# ledboard-r1.net
KiCad netlist of a schematic drawn in EAGLE
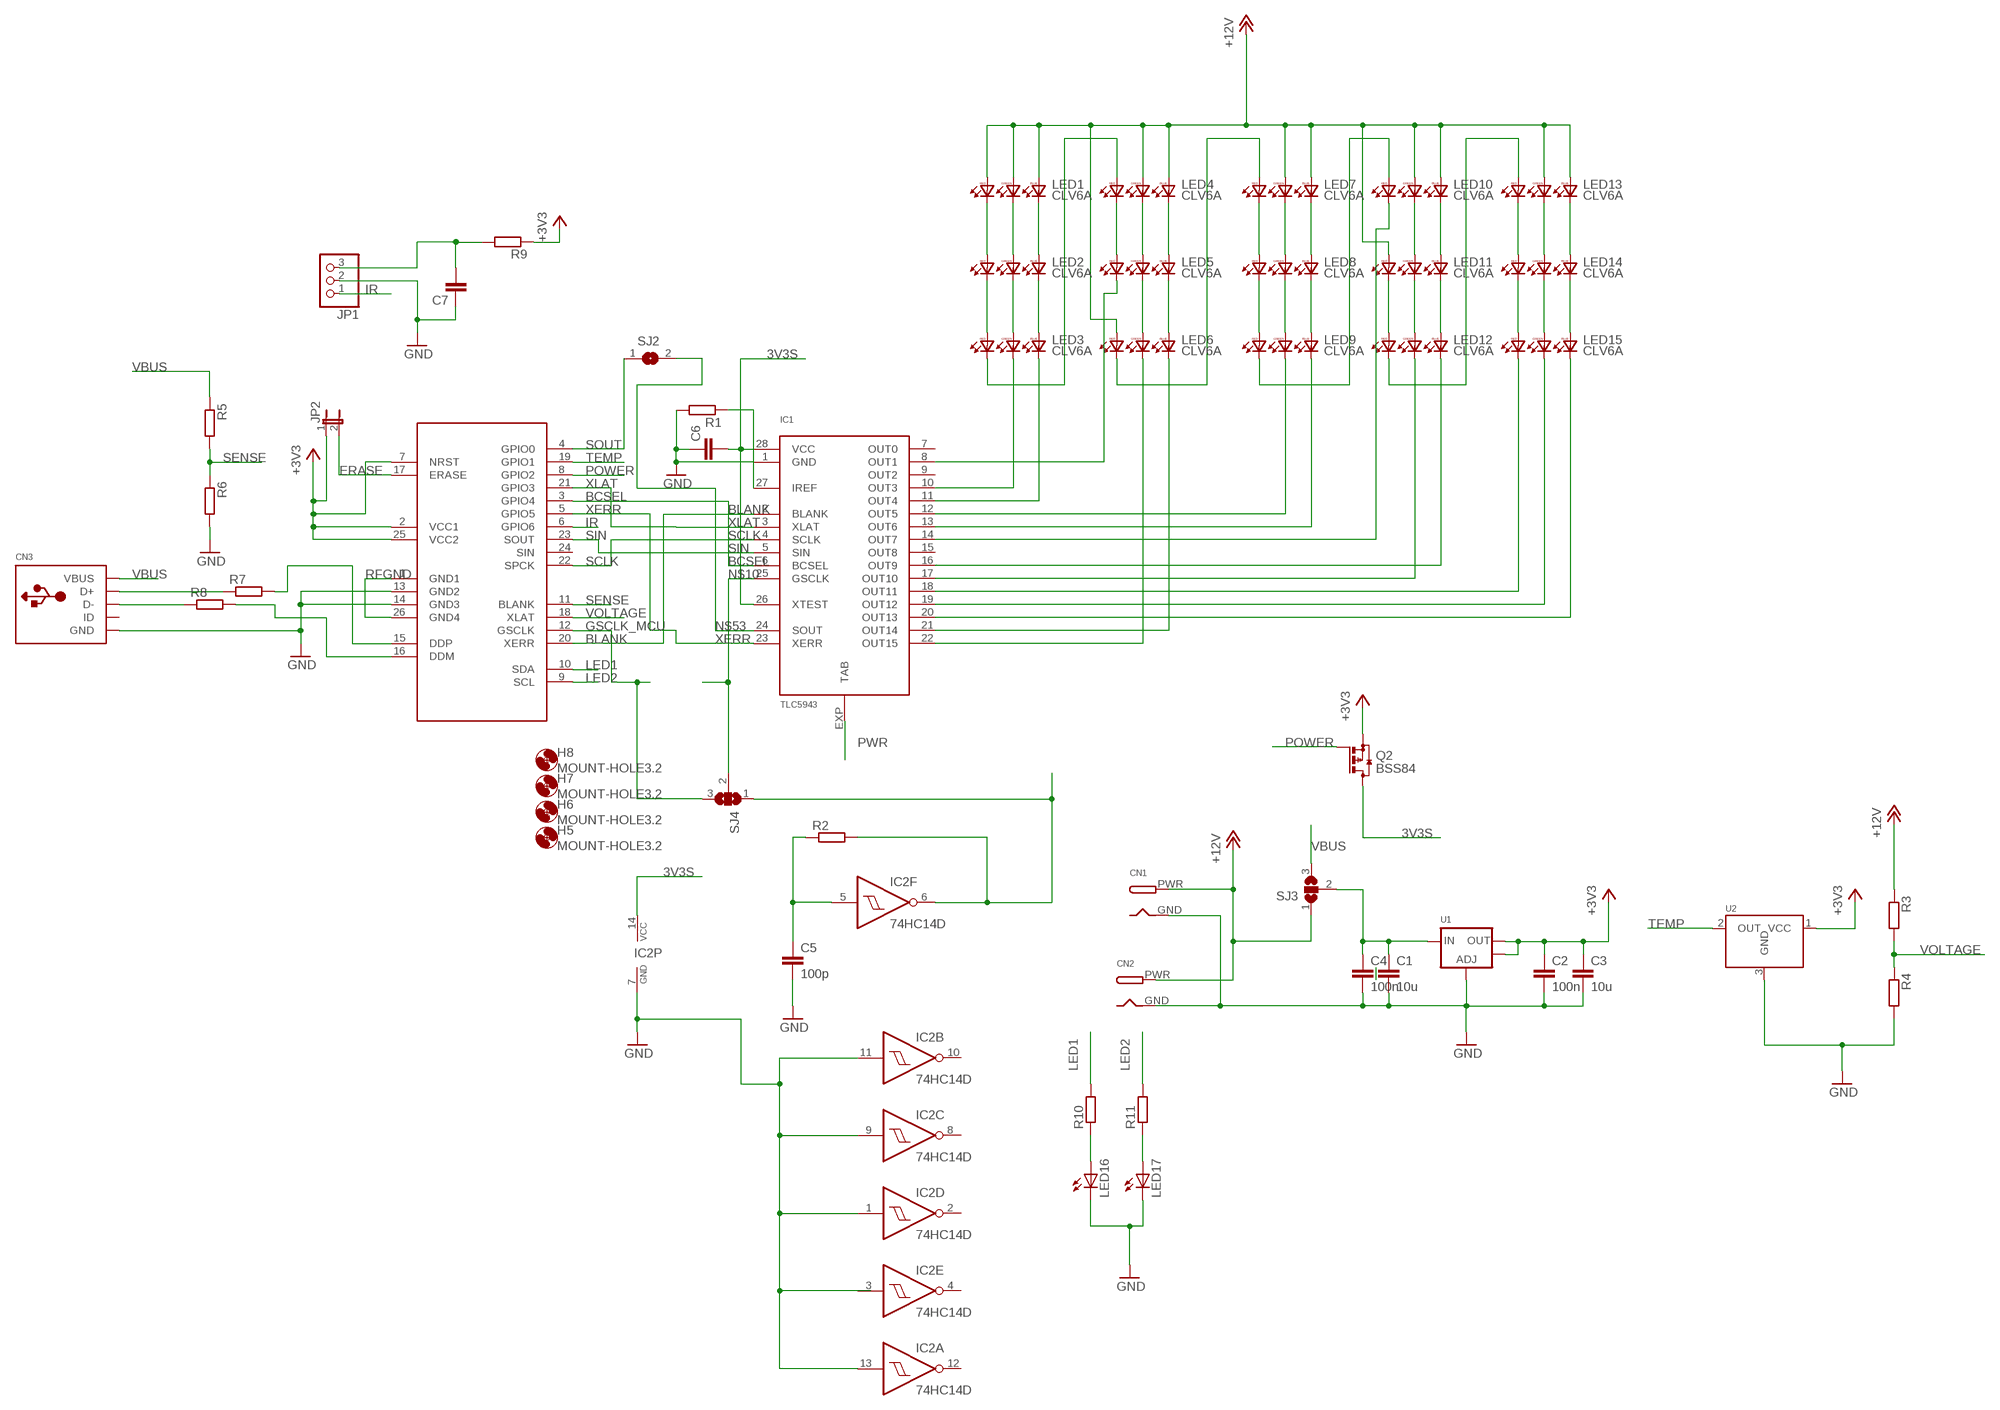
[diagram p0: schematic, sheet 1]

(export (version "E")
  (design (tool "Eeschema 10.0.6"))
  (components
    (comp (ref "C1")
      (value "10u")
      (footprint "eagle-import:C0805")
      (libsource (lib "eagle-import") (part "C-EUC0805"))
    )
    (comp (ref "C2")
      (value "100n")
      (footprint "eagle-import:C0805")
      (libsource (lib "eagle-import") (part "C-EUC0805"))
    )
    (comp (ref "C3")
      (value "10u")
      (footprint "eagle-import:C0805")
      (libsource (lib "eagle-import") (part "C-EUC0805"))
    )
    (comp (ref "C4")
      (value "100n")
      (footprint "eagle-import:C0805")
      (libsource (lib "eagle-import") (part "C-EUC0805"))
    )
    (comp (ref "C5")
      (value "100p")
      (footprint "eagle-import:C0805")
      (libsource (lib "eagle-import") (part "C-EUC0805"))
    )
    (comp (ref "C6")
      (value "C-EUC0805")
      (footprint "eagle-import:C0805")
      (libsource (lib "eagle-import") (part "C-EUC0805"))
    )
    (comp (ref "C7")
      (value "C-EUC0805")
      (footprint "eagle-import:C0805")
      (libsource (lib "eagle-import") (part "C-EUC0805"))
    )
    (comp (ref "CN1")
      (value "DCBARRELPTH")
      (footprint "eagle-import:DCJACK_2MM_PTH")
      (libsource (lib "eagle-import") (part "DCBARRELPTH"))
    )
    (comp (ref "CN2")
      (value "DCBARRELPTH")
      (footprint "eagle-import:DCJACK_2MM_PTH")
      (libsource (lib "eagle-import") (part "DCBARRELPTH"))
    )
    (comp (ref "CN3")
      (value "USBMINIB")
      (footprint "eagle-import:USB-MINIB")
      (libsource (lib "eagle-import") (part "USBMINIB"))
    )
    (comp (ref "H5")
      (value "MOUNT-HOLE3.2")
      (footprint "eagle-import:3,2")
      (libsource (lib "eagle-import") (part "MOUNT-HOLE3.2"))
    )
    (comp (ref "H6")
      (value "MOUNT-HOLE3.2")
      (footprint "eagle-import:3,2")
      (libsource (lib "eagle-import") (part "MOUNT-HOLE3.2"))
    )
    (comp (ref "H7")
      (value "MOUNT-HOLE3.2")
      (footprint "eagle-import:3,2")
      (libsource (lib "eagle-import") (part "MOUNT-HOLE3.2"))
    )
    (comp (ref "H8")
      (value "MOUNT-HOLE3.2")
      (footprint "eagle-import:3,2")
      (libsource (lib "eagle-import") (part "MOUNT-HOLE3.2"))
    )
    (comp (ref "IC1")
      (value "TLC5943")
      (footprint "eagle-import:HTSSOP28PWP")
      (libsource (lib "eagle-import") (part "TLC5943"))
    )
    (comp (ref "IC2")
      (value "74HC14D")
      (footprint "eagle-import:SO14")
      (libsource (lib "eagle-import") (part "7414DHC"))
    )
    (comp (ref "JP1")
      (value "PINHD-1X3")
      (footprint "eagle-import:1X03")
      (libsource (lib "eagle-import") (part "PINHD-1X3"))
    )
    (comp (ref "JP2")
      (value "JP1E")
      (footprint "eagle-import:JP1")
      (libsource (lib "eagle-import") (part "JP1E"))
    )
    (comp (ref "LED1")
      (value "CLV6A")
      (footprint "eagle-import:PLCC6")
      (libsource (lib "eagle-import") (part "CLV6A"))
    )
    (comp (ref "LED2")
      (value "CLV6A")
      (footprint "eagle-import:PLCC6")
      (libsource (lib "eagle-import") (part "CLV6A"))
    )
    (comp (ref "LED3")
      (value "CLV6A")
      (footprint "eagle-import:PLCC6")
      (libsource (lib "eagle-import") (part "CLV6A"))
    )
    (comp (ref "LED4")
      (value "CLV6A")
      (footprint "eagle-import:PLCC6")
      (libsource (lib "eagle-import") (part "CLV6A"))
    )
    (comp (ref "LED5")
      (value "CLV6A")
      (footprint "eagle-import:PLCC6")
      (libsource (lib "eagle-import") (part "CLV6A"))
    )
    (comp (ref "LED6")
      (value "CLV6A")
      (footprint "eagle-import:PLCC6")
      (libsource (lib "eagle-import") (part "CLV6A"))
    )
    (comp (ref "LED7")
      (value "CLV6A")
      (footprint "eagle-import:PLCC6")
      (libsource (lib "eagle-import") (part "CLV6A"))
    )
    (comp (ref "LED8")
      (value "CLV6A")
      (footprint "eagle-import:PLCC6")
      (libsource (lib "eagle-import") (part "CLV6A"))
    )
    (comp (ref "LED9")
      (value "CLV6A")
      (footprint "eagle-import:PLCC6")
      (libsource (lib "eagle-import") (part "CLV6A"))
    )
    (comp (ref "LED10")
      (value "CLV6A")
      (footprint "eagle-import:PLCC6")
      (libsource (lib "eagle-import") (part "CLV6A"))
    )
    (comp (ref "LED11")
      (value "CLV6A")
      (footprint "eagle-import:PLCC6")
      (libsource (lib "eagle-import") (part "CLV6A"))
    )
    (comp (ref "LED12")
      (value "CLV6A")
      (footprint "eagle-import:PLCC6")
      (libsource (lib "eagle-import") (part "CLV6A"))
    )
    (comp (ref "LED13")
      (value "CLV6A")
      (footprint "eagle-import:PLCC6")
      (libsource (lib "eagle-import") (part "CLV6A"))
    )
    (comp (ref "LED14")
      (value "CLV6A")
      (footprint "eagle-import:PLCC6")
      (libsource (lib "eagle-import") (part "CLV6A"))
    )
    (comp (ref "LED15")
      (value "CLV6A")
      (footprint "eagle-import:PLCC6")
      (libsource (lib "eagle-import") (part "CLV6A"))
    )
    (comp (ref "LED16")
      (value "LEDCHIP-LED0805")
      (footprint "eagle-import:CHIP-LED0805")
      (libsource (lib "eagle-import") (part "LEDCHIP-LED0805"))
    )
    (comp (ref "LED17")
      (value "LEDCHIP-LED0805")
      (footprint "eagle-import:CHIP-LED0805")
      (libsource (lib "eagle-import") (part "LEDCHIP-LED0805"))
    )
    (comp (ref "Q2")
      (value "BSS84")
      (footprint "eagle-import:SOT23")
      (libsource (lib "eagle-import") (part "BSS84"))
    )
    (comp (ref "R1")
      (value "R-EU_R0805")
      (footprint "eagle-import:R0805")
      (libsource (lib "eagle-import") (part "R-EU_R0805"))
    )
    (comp (ref "R2")
      (value "R-EU_R0805")
      (footprint "eagle-import:R0805")
      (libsource (lib "eagle-import") (part "R-EU_R0805"))
    )
    (comp (ref "R3")
      (value "R-EU_R0805")
      (footprint "eagle-import:R0805")
      (libsource (lib "eagle-import") (part "R-EU_R0805"))
    )
    (comp (ref "R4")
      (value "R-EU_R0805")
      (footprint "eagle-import:R0805")
      (libsource (lib "eagle-import") (part "R-EU_R0805"))
    )
    (comp (ref "R5")
      (value "R-EU_R0805")
      (footprint "eagle-import:R0805")
      (libsource (lib "eagle-import") (part "R-EU_R0805"))
    )
    (comp (ref "R6")
      (value "R-EU_R0805")
      (footprint "eagle-import:R0805")
      (libsource (lib "eagle-import") (part "R-EU_R0805"))
    )
    (comp (ref "R7")
      (value "R-EU_R0805")
      (footprint "eagle-import:R0805")
      (libsource (lib "eagle-import") (part "R-EU_R0805"))
    )
    (comp (ref "R8")
      (value "R-EU_R0805")
      (footprint "eagle-import:R0805")
      (libsource (lib "eagle-import") (part "R-EU_R0805"))
    )
    (comp (ref "R9")
      (value "R-EU_R0805")
      (footprint "eagle-import:R0805")
      (libsource (lib "eagle-import") (part "R-EU_R0805"))
    )
    (comp (ref "R10")
      (value "R-EU_R0805")
      (footprint "eagle-import:R0805")
      (libsource (lib "eagle-import") (part "R-EU_R0805"))
    )
    (comp (ref "R11")
      (value "R-EU_R0805")
      (footprint "eagle-import:R0805")
      (libsource (lib "eagle-import") (part "R-EU_R0805"))
    )
    (comp (ref "SJ2") (value "SJ") (footprint "eagle-import:SJ") (libsource (lib "eagle-import") (part "SJ")))
    (comp (ref "SJ3")
      (value "SJ2W")
      (footprint "eagle-import:SJ_2")
      (libsource (lib "eagle-import") (part "SJ2W"))
    )
    (comp (ref "SJ4")
      (value "SJ2W")
      (footprint "eagle-import:SJ_2")
      (libsource (lib "eagle-import") (part "SJ2W"))
    )
    (comp (ref "U$1")
      (value "RFBOARD")
      (footprint "eagle-import:RFBOARD")
      (libsource (lib "eagle-import") (part "RFBOARD"))
    )
    (comp (ref "U1")
      (value "LM1117SOT223-REFLOW")
      (footprint "eagle-import:SOT223-R")
      (libsource (lib "eagle-import") (part "LM1117SOT223-REFLOW"))
    )
    (comp (ref "U2")
      (value "MCP9701T-E/TTCTREFLOW")
      (footprint "eagle-import:SOT23-R")
      (libsource (lib "eagle-import") (part "MCP9701T-E/TTCTREFLOW"))
    )
  )
  (nets
    (net (code "1") (name "+3V3") (class "Default")
      (node (ref "C2") (pin "1") (pinfunction "1_1") (pintype "passive"))
      (node (ref "C3") (pin "1") (pinfunction "1_1") (pintype "passive"))
      (node (ref "JP2") (pin "1") (pinfunction "1_1") (pintype "passive"))
      (node (ref "Q2") (pin "2") (pinfunction "S_2") (pintype "passive"))
      (node (ref "R9") (pin "1") (pinfunction "1_1") (pintype "passive"))
      (node (ref "U$1") (pin "2") (pinfunction "VCC1_2") (pintype "bidirectional"))
      (node (ref "U$1") (pin "25") (pinfunction "VCC2_25") (pintype "bidirectional"))
      (node (ref "U$1") (pin "7") (pinfunction "NRST_7") (pintype "bidirectional"))
      (node (ref "U1") (pin "2") (pinfunction "OUT_2") (pintype "passive"))
      (node (ref "U1") (pin "4") (pinfunction "OUT1_4") (pintype "passive"))
      (node (ref "U2") (pin "1") (pinfunction "VCC_1") (pintype "power_in"))
    )
    (net (code "2") (name "+12V") (class "Default")
      (node (ref "CN1") (pin "PWR") (pinfunction "PWR_PWR") (pintype "power_in"))
      (node (ref "CN2") (pin "PWR") (pinfunction "PWR_PWR") (pintype "power_in"))
      (node (ref "LED1") (pin "4") (pinfunction "RA_4") (pintype "passive"))
      (node (ref "LED1") (pin "5") (pinfunction "GA_5") (pintype "passive"))
      (node (ref "LED1") (pin "6") (pinfunction "BA_6") (pintype "passive"))
      (node (ref "LED10") (pin "5") (pinfunction "GA_5") (pintype "passive"))
      (node (ref "LED10") (pin "6") (pinfunction "BA_6") (pintype "passive"))
      (node (ref "LED11") (pin "4") (pinfunction "RA_4") (pintype "passive"))
      (node (ref "LED13") (pin "5") (pinfunction "GA_5") (pintype "passive"))
      (node (ref "LED13") (pin "6") (pinfunction "BA_6") (pintype "passive"))
      (node (ref "LED4") (pin "5") (pinfunction "GA_5") (pintype "passive"))
      (node (ref "LED4") (pin "6") (pinfunction "BA_6") (pintype "passive"))
      (node (ref "LED6") (pin "4") (pinfunction "RA_4") (pintype "passive"))
      (node (ref "LED7") (pin "5") (pinfunction "GA_5") (pintype "passive"))
      (node (ref "LED7") (pin "6") (pinfunction "BA_6") (pintype "passive"))
      (node (ref "R3") (pin "1") (pinfunction "1_1") (pintype "passive"))
      (node (ref "SJ3") (pin "1") (pinfunction "1_1") (pintype "passive"))
    )
    (net (code "3") (name "/3V3S") (class "Default")
      (node (ref "C6") (pin "2") (pinfunction "2_2") (pintype "passive"))
      (node (ref "IC1") (pin "26") (pinfunction "XTEST_26") (pintype "bidirectional"))
      (node (ref "IC1") (pin "28") (pinfunction "VCC_28") (pintype "bidirectional"))
      (node (ref "IC2") (pin "14") (pinfunction "VCC_14") (pintype "power_in"))
      (node (ref "Q2") (pin "3") (pinfunction "D_3") (pintype "passive"))
    )
    (net (code "4") (name "/BCSEL") (class "Default")
      (node (ref "IC1") (pin "6") (pinfunction "BCSEL_6") (pintype "bidirectional"))
      (node (ref "U$1") (pin "3") (pinfunction "GPIO4_3") (pintype "bidirectional"))
    )
    (net (code "5") (name "/BLANK") (class "Default")
      (node (ref "IC1") (pin "2") (pinfunction "BLANK_2") (pintype "bidirectional"))
      (node (ref "U$1") (pin "20") (pinfunction "XERR_20") (pintype "bidirectional"))
    )
    (net (code "6") (name "/ERASE") (class "Default")
      (node (ref "JP2") (pin "2") (pinfunction "2_2") (pintype "passive"))
      (node (ref "U$1") (pin "17") (pinfunction "ERASE_17") (pintype "bidirectional"))
    )
    (net (code "7") (name "/GSCLK_MCU") (class "Default")
      (node (ref "SJ4") (pin "3") (pinfunction "3_3") (pintype "passive"))
      (node (ref "U$1") (pin "12") (pinfunction "GSCLK_12") (pintype "bidirectional"))
    )
    (net (code "8") (name "/IR") (class "Default")
      (node (ref "JP1") (pin "1") (pinfunction "1_1") (pintype "passive"))
      (node (ref "U$1") (pin "6") (pinfunction "GPIO6_6") (pintype "bidirectional"))
    )
    (net (code "9") (name "/LED1") (class "Default")
      (node (ref "R10") (pin "2") (pinfunction "2_2") (pintype "passive"))
      (node (ref "U$1") (pin "10") (pinfunction "SDA_10") (pintype "bidirectional"))
    )
    (net (code "10") (name "/LED2") (class "Default")
      (node (ref "R11") (pin "2") (pinfunction "2_2") (pintype "passive"))
      (node (ref "U$1") (pin "9") (pinfunction "SCL_9") (pintype "bidirectional"))
    )
    (net (code "11") (name "/N$10") (class "Default")
      (node (ref "IC1") (pin "25") (pinfunction "GSCLK_25") (pintype "bidirectional"))
      (node (ref "SJ4") (pin "2") (pinfunction "2_2") (pintype "passive"))
    )
    (net (code "12") (name "/N$53") (class "Default")
      (node (ref "IC1") (pin "24") (pinfunction "SOUT_24") (pintype "bidirectional"))
      (node (ref "SJ2") (pin "2") (pinfunction "2_2") (pintype "passive"))
    )
    (net (code "13") (name "/POWER") (class "Default")
      (node (ref "Q2") (pin "1") (pinfunction "G_1") (pintype "passive"))
      (node (ref "U$1") (pin "8") (pinfunction "GPIO2_8") (pintype "bidirectional"))
    )
    (net (code "14") (name "/PWR") (class "Default")
      (node (ref "IC1") (pin "EXP") (pinfunction "TAB_EXP") (pintype "bidirectional"))
    )
    (net (code "15") (name "/RFGND") (class "Default")
      (node (ref "U$1") (pin "1") (pinfunction "GND1_1") (pintype "bidirectional"))
      (node (ref "U$1") (pin "26") (pinfunction "GND4_26") (pintype "bidirectional"))
    )
    (net (code "16") (name "/SCLK") (class "Default")
      (node (ref "IC1") (pin "4") (pinfunction "SCLK_4") (pintype "bidirectional"))
      (node (ref "U$1") (pin "22") (pinfunction "SPCK_22") (pintype "bidirectional"))
    )
    (net (code "17") (name "/SENSE") (class "Default")
      (node (ref "R5") (pin "2") (pinfunction "2_2") (pintype "passive"))
      (node (ref "R6") (pin "1") (pinfunction "1_1") (pintype "passive"))
      (node (ref "U$1") (pin "11") (pinfunction "BLANK_11") (pintype "bidirectional"))
    )
    (net (code "18") (name "/SIN") (class "Default")
      (node (ref "IC1") (pin "5") (pinfunction "SIN_5") (pintype "bidirectional"))
      (node (ref "U$1") (pin "23") (pinfunction "SOUT_23") (pintype "bidirectional"))
    )
    (net (code "19") (name "/SOUT") (class "Default")
      (node (ref "SJ2") (pin "1") (pinfunction "1_1") (pintype "passive"))
      (node (ref "U$1") (pin "4") (pinfunction "GPIO0_4") (pintype "bidirectional"))
    )
    (net (code "20") (name "/TEMP") (class "Default")
      (node (ref "U$1") (pin "19") (pinfunction "GPIO1_19") (pintype "bidirectional"))
      (node (ref "U2") (pin "2") (pinfunction "OUT_2") (pintype "bidirectional"))
    )
    (net (code "21") (name "/VBUS") (class "Default")
      (node (ref "CN3") (pin "VBUS") (pinfunction "VBUS_VBUS") (pintype "power_in"))
      (node (ref "R5") (pin "1") (pinfunction "1_1") (pintype "passive"))
      (node (ref "SJ3") (pin "3") (pinfunction "3_3") (pintype "passive"))
    )
    (net (code "22") (name "/VOLTAGE") (class "Default")
      (node (ref "R3") (pin "2") (pinfunction "2_2") (pintype "passive"))
      (node (ref "R4") (pin "1") (pinfunction "1_1") (pintype "passive"))
      (node (ref "U$1") (pin "18") (pinfunction "XLAT_18") (pintype "bidirectional"))
    )
    (net (code "23") (name "/XERR") (class "Default")
      (node (ref "IC1") (pin "23") (pinfunction "XERR_23") (pintype "bidirectional"))
      (node (ref "U$1") (pin "5") (pinfunction "GPIO5_5") (pintype "bidirectional"))
    )
    (net (code "24") (name "/XLAT") (class "Default")
      (node (ref "IC1") (pin "3") (pinfunction "XLAT_3") (pintype "bidirectional"))
      (node (ref "U$1") (pin "21") (pinfunction "GPIO3_21") (pintype "bidirectional"))
    )
    (net (code "25") (name "GND") (class "Default")
      (node (ref "C1") (pin "2") (pinfunction "2_2") (pintype "passive"))
      (node (ref "C2") (pin "2") (pinfunction "2_2") (pintype "passive"))
      (node (ref "C3") (pin "2") (pinfunction "2_2") (pintype "passive"))
      (node (ref "C4") (pin "2") (pinfunction "2_2") (pintype "passive"))
      (node (ref "C5") (pin "2") (pinfunction "2_2") (pintype "passive"))
      (node (ref "C6") (pin "1") (pinfunction "1_1") (pintype "passive"))
      (node (ref "C7") (pin "1") (pinfunction "1_1") (pintype "passive"))
      (node (ref "CN1") (pin "GND") (pinfunction "GND_GND") (pintype "power_in"))
      (node (ref "CN2") (pin "GND") (pinfunction "GND_GND") (pintype "power_in"))
      (node (ref "CN3") (pin "GND") (pinfunction "GND_GND") (pintype "power_in"))
      (node (ref "IC1") (pin "1") (pinfunction "GND_1") (pintype "bidirectional"))
      (node (ref "IC2") (pin "1") (pinfunction "I_1") (pintype "input"))
      (node (ref "IC2") (pin "11") (pinfunction "I_11") (pintype "input"))
      (node (ref "IC2") (pin "13") (pinfunction "I_13") (pintype "input"))
      (node (ref "IC2") (pin "7") (pinfunction "GND_7") (pintype "power_in"))
      (node (ref "IC2") (pin "9") (pinfunction "I_9") (pintype "input"))
      (node (ref "JP1") (pin "2") (pinfunction "2_2") (pintype "passive"))
      (node (ref "LED16") (pin "C") (pinfunction "C_C") (pintype "passive"))
      (node (ref "LED17") (pin "C") (pinfunction "C_C") (pintype "passive"))
      (node (ref "R1") (pin "2") (pinfunction "2_2") (pintype "passive"))
      (node (ref "R4") (pin "2") (pinfunction "2_2") (pintype "passive"))
      (node (ref "R6") (pin "2") (pinfunction "2_2") (pintype "passive"))
      (node (ref "U$1") (pin "13") (pinfunction "GND2_13") (pintype "bidirectional"))
      (node (ref "U$1") (pin "14") (pinfunction "GND3_14") (pintype "bidirectional"))
      (node (ref "U1") (pin "1") (pinfunction "ADJ_1") (pintype "input"))
      (node (ref "U2") (pin "3") (pinfunction "GND_3") (pintype "power_in"))
    )
    (net (code "26") (name "Net-(C7-Pad2)") (class "Default")
      (node (ref "C7") (pin "2") (pinfunction "2_2") (pintype "passive"))
      (node (ref "JP1") (pin "3") (pinfunction "3_3") (pintype "passive"))
      (node (ref "R9") (pin "2") (pinfunction "2_2") (pintype "passive"))
    )
    (net (code "27") (name "Net-(CN3-PadD+)") (class "Default")
      (node (ref "CN3") (pin "D+") (pinfunction "D+_D+") (pintype "bidirectional"))
      (node (ref "R7") (pin "1") (pinfunction "1_1") (pintype "passive"))
    )
    (net (code "28") (name "Net-(CN3-PadD-)") (class "Default")
      (node (ref "CN3") (pin "D-") (pinfunction "D-_D-") (pintype "bidirectional"))
      (node (ref "R8") (pin "1") (pinfunction "1_1") (pintype "passive"))
    )
    (net (code "29") (name "Net-(IC1-IREF)") (class "Default")
      (node (ref "IC1") (pin "27") (pinfunction "IREF_27") (pintype "bidirectional"))
      (node (ref "R1") (pin "1") (pinfunction "1_1") (pintype "passive"))
    )
    (net (code "30") (name "Net-(IC1-OUT1)") (class "Default")
      (node (ref "IC1") (pin "8") (pinfunction "OUT1_8") (pintype "bidirectional"))
      (node (ref "LED5") (pin "3") (pinfunction "RC_3") (pintype "passive"))
    )
    (net (code "31") (name "Net-(IC1-OUT3)") (class "Default")
      (node (ref "IC1") (pin "10") (pinfunction "OUT3_10") (pintype "bidirectional"))
      (node (ref "LED3") (pin "2") (pinfunction "GC_2") (pintype "passive"))
    )
    (net (code "32") (name "Net-(IC1-OUT4)") (class "Default")
      (node (ref "IC1") (pin "11") (pinfunction "OUT4_11") (pintype "bidirectional"))
      (node (ref "LED3") (pin "1") (pinfunction "BC_1") (pintype "passive"))
    )
    (net (code "33") (name "Net-(IC1-OUT5)") (class "Default")
      (node (ref "IC1") (pin "12") (pinfunction "OUT5_12") (pintype "bidirectional"))
      (node (ref "LED9") (pin "2") (pinfunction "GC_2") (pintype "passive"))
    )
    (net (code "34") (name "Net-(IC1-OUT6)") (class "Default")
      (node (ref "IC1") (pin "13") (pinfunction "OUT6_13") (pintype "bidirectional"))
      (node (ref "LED9") (pin "1") (pinfunction "BC_1") (pintype "passive"))
    )
    (net (code "35") (name "Net-(IC1-OUT7)") (class "Default")
      (node (ref "IC1") (pin "14") (pinfunction "OUT7_14") (pintype "bidirectional"))
      (node (ref "LED10") (pin "3") (pinfunction "RC_3") (pintype "passive"))
    )
    (net (code "36") (name "Net-(IC1-OUT9)") (class "Default")
      (node (ref "IC1") (pin "16") (pinfunction "OUT9_16") (pintype "bidirectional"))
      (node (ref "LED12") (pin "1") (pinfunction "BC_1") (pintype "passive"))
    )
    (net (code "37") (name "Net-(IC1-OUT10)") (class "Default")
      (node (ref "IC1") (pin "17") (pinfunction "OUT10_17") (pintype "bidirectional"))
      (node (ref "LED12") (pin "2") (pinfunction "GC_2") (pintype "passive"))
    )
    (net (code "38") (name "Net-(IC1-OUT11)") (class "Default")
      (node (ref "IC1") (pin "18") (pinfunction "OUT11_18") (pintype "bidirectional"))
      (node (ref "LED15") (pin "3") (pinfunction "RC_3") (pintype "passive"))
    )
    (net (code "39") (name "Net-(IC1-OUT12)") (class "Default")
      (node (ref "IC1") (pin "19") (pinfunction "OUT12_19") (pintype "bidirectional"))
      (node (ref "LED15") (pin "2") (pinfunction "GC_2") (pintype "passive"))
    )
    (net (code "40") (name "Net-(IC1-OUT13)") (class "Default")
      (node (ref "IC1") (pin "20") (pinfunction "OUT13_20") (pintype "bidirectional"))
      (node (ref "LED15") (pin "1") (pinfunction "BC_1") (pintype "passive"))
    )
    (net (code "41") (name "Net-(IC1-OUT14)") (class "Default")
      (node (ref "IC1") (pin "21") (pinfunction "OUT14_21") (pintype "bidirectional"))
      (node (ref "LED6") (pin "1") (pinfunction "BC_1") (pintype "passive"))
    )
    (net (code "42") (name "Net-(IC1-OUT15)") (class "Default")
      (node (ref "IC1") (pin "22") (pinfunction "OUT15_22") (pintype "bidirectional"))
      (node (ref "LED6") (pin "2") (pinfunction "GC_2") (pintype "passive"))
    )
    (net (code "43") (name "Net-(IC2F-I)") (class "Default")
      (node (ref "C5") (pin "1") (pinfunction "1_1") (pintype "passive"))
      (node (ref "IC2") (pin "5") (pinfunction "I_5") (pintype "input"))
      (node (ref "R2") (pin "1") (pinfunction "1_1") (pintype "passive"))
    )
    (net (code "44") (name "Net-(IC2F-O)") (class "Default")
      (node (ref "IC2") (pin "6") (pinfunction "O_6") (pintype "output"))
      (node (ref "R2") (pin "2") (pinfunction "2_2") (pintype "passive"))
      (node (ref "SJ4") (pin "1") (pinfunction "1_1") (pintype "passive"))
    )
    (net (code "45") (name "Net-(LED1-BC)") (class "Default")
      (node (ref "LED1") (pin "1") (pinfunction "BC_1") (pintype "passive"))
      (node (ref "LED2") (pin "6") (pinfunction "BA_6") (pintype "passive"))
    )
    (net (code "46") (name "Net-(LED1-GC)") (class "Default")
      (node (ref "LED1") (pin "2") (pinfunction "GC_2") (pintype "passive"))
      (node (ref "LED2") (pin "5") (pinfunction "GA_5") (pintype "passive"))
    )
    (net (code "47") (name "Net-(LED1-RC)") (class "Default")
      (node (ref "LED1") (pin "3") (pinfunction "RC_3") (pintype "passive"))
      (node (ref "LED2") (pin "4") (pinfunction "RA_4") (pintype "passive"))
    )
    (net (code "48") (name "Net-(LED2-BC)") (class "Default")
      (node (ref "LED2") (pin "1") (pinfunction "BC_1") (pintype "passive"))
      (node (ref "LED3") (pin "6") (pinfunction "BA_6") (pintype "passive"))
    )
    (net (code "49") (name "Net-(LED2-GC)") (class "Default")
      (node (ref "LED2") (pin "2") (pinfunction "GC_2") (pintype "passive"))
      (node (ref "LED3") (pin "5") (pinfunction "GA_5") (pintype "passive"))
    )
    (net (code "50") (name "Net-(LED2-RC)") (class "Default")
      (node (ref "LED2") (pin "3") (pinfunction "RC_3") (pintype "passive"))
      (node (ref "LED3") (pin "4") (pinfunction "RA_4") (pintype "passive"))
    )
    (net (code "51") (name "Net-(LED3-RC)") (class "Default")
      (node (ref "LED3") (pin "3") (pinfunction "RC_3") (pintype "passive"))
      (node (ref "LED4") (pin "4") (pinfunction "RA_4") (pintype "passive"))
    )
    (net (code "52") (name "Net-(LED4-BC)") (class "Default")
      (node (ref "LED4") (pin "1") (pinfunction "BC_1") (pintype "passive"))
      (node (ref "LED5") (pin "6") (pinfunction "BA_6") (pintype "passive"))
    )
    (net (code "53") (name "Net-(LED4-GC)") (class "Default")
      (node (ref "LED4") (pin "2") (pinfunction "GC_2") (pintype "passive"))
      (node (ref "LED5") (pin "5") (pinfunction "GA_5") (pintype "passive"))
    )
    (net (code "54") (name "Net-(LED4-RC)") (class "Default")
      (node (ref "LED4") (pin "3") (pinfunction "RC_3") (pintype "passive"))
      (node (ref "LED5") (pin "4") (pinfunction "RA_4") (pintype "passive"))
    )
    (net (code "55") (name "Net-(LED5-BC)") (class "Default")
      (node (ref "LED5") (pin "1") (pinfunction "BC_1") (pintype "passive"))
      (node (ref "LED6") (pin "6") (pinfunction "BA_6") (pintype "passive"))
    )
    (net (code "56") (name "Net-(LED5-GC)") (class "Default")
      (node (ref "LED5") (pin "2") (pinfunction "GC_2") (pintype "passive"))
      (node (ref "LED6") (pin "5") (pinfunction "GA_5") (pintype "passive"))
    )
    (net (code "57") (name "Net-(LED6-RC)") (class "Default")
      (node (ref "LED6") (pin "3") (pinfunction "RC_3") (pintype "passive"))
      (node (ref "LED7") (pin "4") (pinfunction "RA_4") (pintype "passive"))
    )
    (net (code "58") (name "Net-(LED7-BC)") (class "Default")
      (node (ref "LED7") (pin "1") (pinfunction "BC_1") (pintype "passive"))
      (node (ref "LED8") (pin "6") (pinfunction "BA_6") (pintype "passive"))
    )
    (net (code "59") (name "Net-(LED7-GC)") (class "Default")
      (node (ref "LED7") (pin "2") (pinfunction "GC_2") (pintype "passive"))
      (node (ref "LED8") (pin "5") (pinfunction "GA_5") (pintype "passive"))
    )
    (net (code "60") (name "Net-(LED7-RC)") (class "Default")
      (node (ref "LED7") (pin "3") (pinfunction "RC_3") (pintype "passive"))
      (node (ref "LED8") (pin "4") (pinfunction "RA_4") (pintype "passive"))
    )
    (net (code "61") (name "Net-(LED8-BC)") (class "Default")
      (node (ref "LED8") (pin "1") (pinfunction "BC_1") (pintype "passive"))
      (node (ref "LED9") (pin "6") (pinfunction "BA_6") (pintype "passive"))
    )
    (net (code "62") (name "Net-(LED8-GC)") (class "Default")
      (node (ref "LED8") (pin "2") (pinfunction "GC_2") (pintype "passive"))
      (node (ref "LED9") (pin "5") (pinfunction "GA_5") (pintype "passive"))
    )
    (net (code "63") (name "Net-(LED8-RC)") (class "Default")
      (node (ref "LED8") (pin "3") (pinfunction "RC_3") (pintype "passive"))
      (node (ref "LED9") (pin "4") (pinfunction "RA_4") (pintype "passive"))
    )
    (net (code "64") (name "Net-(LED10-BC)") (class "Default")
      (node (ref "LED10") (pin "1") (pinfunction "BC_1") (pintype "passive"))
      (node (ref "LED11") (pin "6") (pinfunction "BA_6") (pintype "passive"))
    )
    (net (code "65") (name "Net-(LED10-GC)") (class "Default")
      (node (ref "LED10") (pin "2") (pinfunction "GC_2") (pintype "passive"))
      (node (ref "LED11") (pin "5") (pinfunction "GA_5") (pintype "passive"))
    )
    (net (code "66") (name "Net-(LED10-RA)") (class "Default")
      (node (ref "LED10") (pin "4") (pinfunction "RA_4") (pintype "passive"))
      (node (ref "LED9") (pin "3") (pinfunction "RC_3") (pintype "passive"))
    )
    (net (code "67") (name "Net-(LED11-BC)") (class "Default")
      (node (ref "LED11") (pin "1") (pinfunction "BC_1") (pintype "passive"))
      (node (ref "LED12") (pin "6") (pinfunction "BA_6") (pintype "passive"))
    )
    (net (code "68") (name "Net-(LED11-GC)") (class "Default")
      (node (ref "LED11") (pin "2") (pinfunction "GC_2") (pintype "passive"))
      (node (ref "LED12") (pin "5") (pinfunction "GA_5") (pintype "passive"))
    )
    (net (code "69") (name "Net-(LED11-RC)") (class "Default")
      (node (ref "LED11") (pin "3") (pinfunction "RC_3") (pintype "passive"))
      (node (ref "LED12") (pin "4") (pinfunction "RA_4") (pintype "passive"))
    )
    (net (code "70") (name "Net-(LED12-RC)") (class "Default")
      (node (ref "LED12") (pin "3") (pinfunction "RC_3") (pintype "passive"))
      (node (ref "LED13") (pin "4") (pinfunction "RA_4") (pintype "passive"))
    )
    (net (code "71") (name "Net-(LED13-BC)") (class "Default")
      (node (ref "LED13") (pin "1") (pinfunction "BC_1") (pintype "passive"))
      (node (ref "LED14") (pin "6") (pinfunction "BA_6") (pintype "passive"))
    )
    (net (code "72") (name "Net-(LED13-GC)") (class "Default")
      (node (ref "LED13") (pin "2") (pinfunction "GC_2") (pintype "passive"))
      (node (ref "LED14") (pin "5") (pinfunction "GA_5") (pintype "passive"))
    )
    (net (code "73") (name "Net-(LED13-RC)") (class "Default")
      (node (ref "LED13") (pin "3") (pinfunction "RC_3") (pintype "passive"))
      (node (ref "LED14") (pin "4") (pinfunction "RA_4") (pintype "passive"))
    )
    (net (code "74") (name "Net-(LED14-BC)") (class "Default")
      (node (ref "LED14") (pin "1") (pinfunction "BC_1") (pintype "passive"))
      (node (ref "LED15") (pin "6") (pinfunction "BA_6") (pintype "passive"))
    )
    (net (code "75") (name "Net-(LED14-GC)") (class "Default")
      (node (ref "LED14") (pin "2") (pinfunction "GC_2") (pintype "passive"))
      (node (ref "LED15") (pin "5") (pinfunction "GA_5") (pintype "passive"))
    )
    (net (code "76") (name "Net-(LED14-RC)") (class "Default")
      (node (ref "LED14") (pin "3") (pinfunction "RC_3") (pintype "passive"))
      (node (ref "LED15") (pin "4") (pinfunction "RA_4") (pintype "passive"))
    )
    (net (code "77") (name "Net-(LED16-PadA)") (class "Default")
      (node (ref "LED16") (pin "A") (pinfunction "A_A") (pintype "passive"))
      (node (ref "R10") (pin "1") (pinfunction "1_1") (pintype "passive"))
    )
    (net (code "78") (name "Net-(LED17-PadA)") (class "Default")
      (node (ref "LED17") (pin "A") (pinfunction "A_A") (pintype "passive"))
      (node (ref "R11") (pin "1") (pinfunction "1_1") (pintype "passive"))
    )
    (net (code "79") (name "Net-(U$1-DDM)") (class "Default")
      (node (ref "R8") (pin "2") (pinfunction "2_2") (pintype "passive"))
      (node (ref "U$1") (pin "16") (pinfunction "DDM_16") (pintype "bidirectional"))
    )
    (net (code "80") (name "Net-(U$1-DDP)") (class "Default")
      (node (ref "R7") (pin "2") (pinfunction "2_2") (pintype "passive"))
      (node (ref "U$1") (pin "15") (pinfunction "DDP_15") (pintype "bidirectional"))
    )
    (net (code "81") (name "Net-(U1-IN)") (class "Default")
      (node (ref "C1") (pin "1") (pinfunction "1_1") (pintype "passive"))
      (node (ref "C4") (pin "1") (pinfunction "1_1") (pintype "passive"))
      (node (ref "SJ3") (pin "2") (pinfunction "2_2") (pintype "passive"))
      (node (ref "U1") (pin "3") (pinfunction "IN_3") (pintype "input"))
    )
    (net (code "82") (name "unconnected-(CN3-PadID)") (class "Default")
      (node (ref "CN3") (pin "ID") (pinfunction "ID_ID") (pintype "bidirectional"))
    )
    (net (code "83") (name "unconnected-(IC1-OUT0-Pad7)") (class "Default")
      (node (ref "IC1") (pin "7") (pinfunction "OUT0_7") (pintype "bidirectional"))
    )
    (net (code "84") (name "unconnected-(IC1-OUT2-Pad9)") (class "Default")
      (node (ref "IC1") (pin "9") (pinfunction "OUT2_9") (pintype "bidirectional"))
    )
    (net (code "85") (name "unconnected-(IC1-OUT8-Pad15)") (class "Default")
      (node (ref "IC1") (pin "15") (pinfunction "OUT8_15") (pintype "bidirectional"))
    )
    (net (code "86") (name "unconnected-(IC2A-O-Pad12)") (class "Default")
      (node (ref "IC2") (pin "12") (pinfunction "O_12") (pintype "output"))
    )
    (net (code "87") (name "unconnected-(IC2B-O-Pad10)") (class "Default")
      (node (ref "IC2") (pin "10") (pinfunction "O_10") (pintype "output"))
    )
    (net (code "88") (name "unconnected-(IC2C-O-Pad8)") (class "Default")
      (node (ref "IC2") (pin "8") (pinfunction "O_8") (pintype "output"))
    )
    (net (code "89") (name "unconnected-(IC2D-O-Pad2)") (class "Default")
      (node (ref "IC2") (pin "2") (pinfunction "O_2") (pintype "output"))
    )
    (net (code "90") (name "unconnected-(IC2E-I-Pad3)") (class "Default")
      (node (ref "IC2") (pin "3") (pinfunction "I_3") (pintype "input"))
    )
    (net (code "91") (name "unconnected-(IC2E-O-Pad4)") (class "Default")
      (node (ref "IC2") (pin "4") (pinfunction "O_4") (pintype "output"))
    )
    (net (code "92") (name "unconnected-(U$1-SIN-Pad24)") (class "Default")
      (node (ref "U$1") (pin "24") (pinfunction "SIN_24") (pintype "bidirectional"))
    )
  )
)
